# 1A20J13_1A21J9_A.net
KiCad netlist of a schematic drawn in Altium Designer
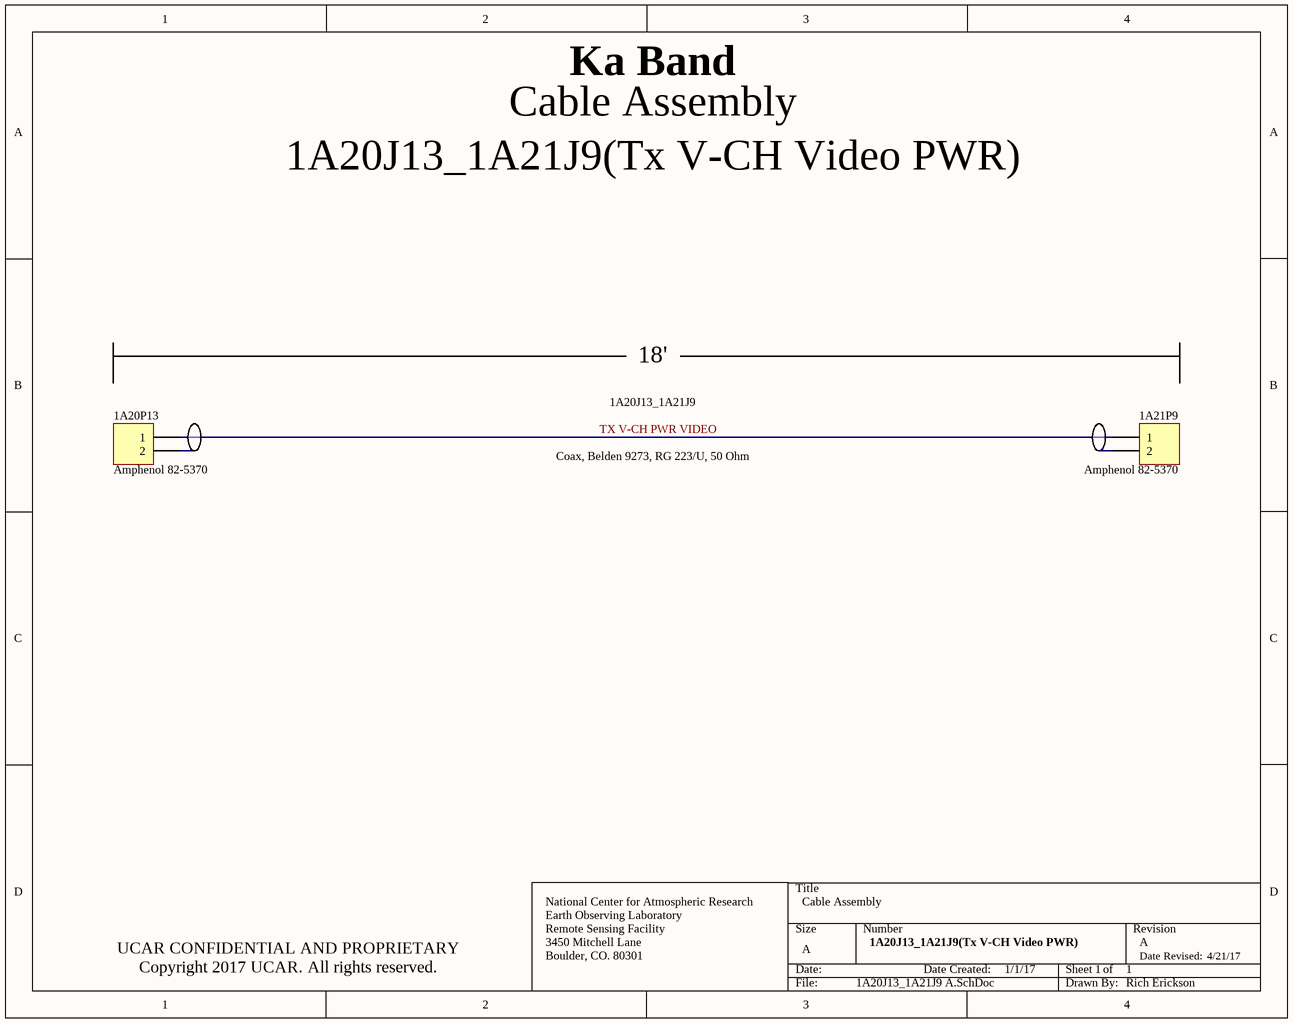
[diagram p0: 1A20J13_1A21J9 A.SchDoc]

(export (version "E")
  (design (tool "Eeschema 10.0.6"))
  (components
    (comp (ref "1A20P13")
      (value "Amphenol 82-5370")
      (footprint "HDR1X2")
      (description "Header, 2-Pin")
      (fields (field (name "PUBLISHER") "Altium Limited"))
      (libsource (lib "Miscellaneous Connectors") (part "Header 2"))
    )
    (comp (ref "1A21P9")
      (value "Amphenol 82-5370")
      (footprint "HDR1X2")
      (description "Header, 2-Pin")
      (fields (field (name "PUBLISHER") "Altium Limited"))
      (libsource (lib "") (part "Header 2_1"))
    )
  )
  (nets
    (net (code "1") (name "/TX V-CH PWR VIDEO") (class "Default")
      (node (ref "1A20P13") (pin "1") (pinfunction "1_1") (pintype "passive"))
      (node (ref "1A21P9") (pin "1") (pinfunction "1_1") (pintype "passive"))
    )
    (net (code "2") (name "unconnected-(1A20P13-Pad2)") (class "Default")
      (node (ref "1A20P13") (pin "2") (pinfunction "2_2") (pintype "passive"))
    )
    (net (code "3") (name "unconnected-(1A21P9-Pad2)") (class "Default")
      (node (ref "1A21P9") (pin "2") (pinfunction "2_2") (pintype "passive"))
    )
  )
)
